# VIC20_Diag_UP.net
KiCad netlist of a schematic drawn in EAGLE
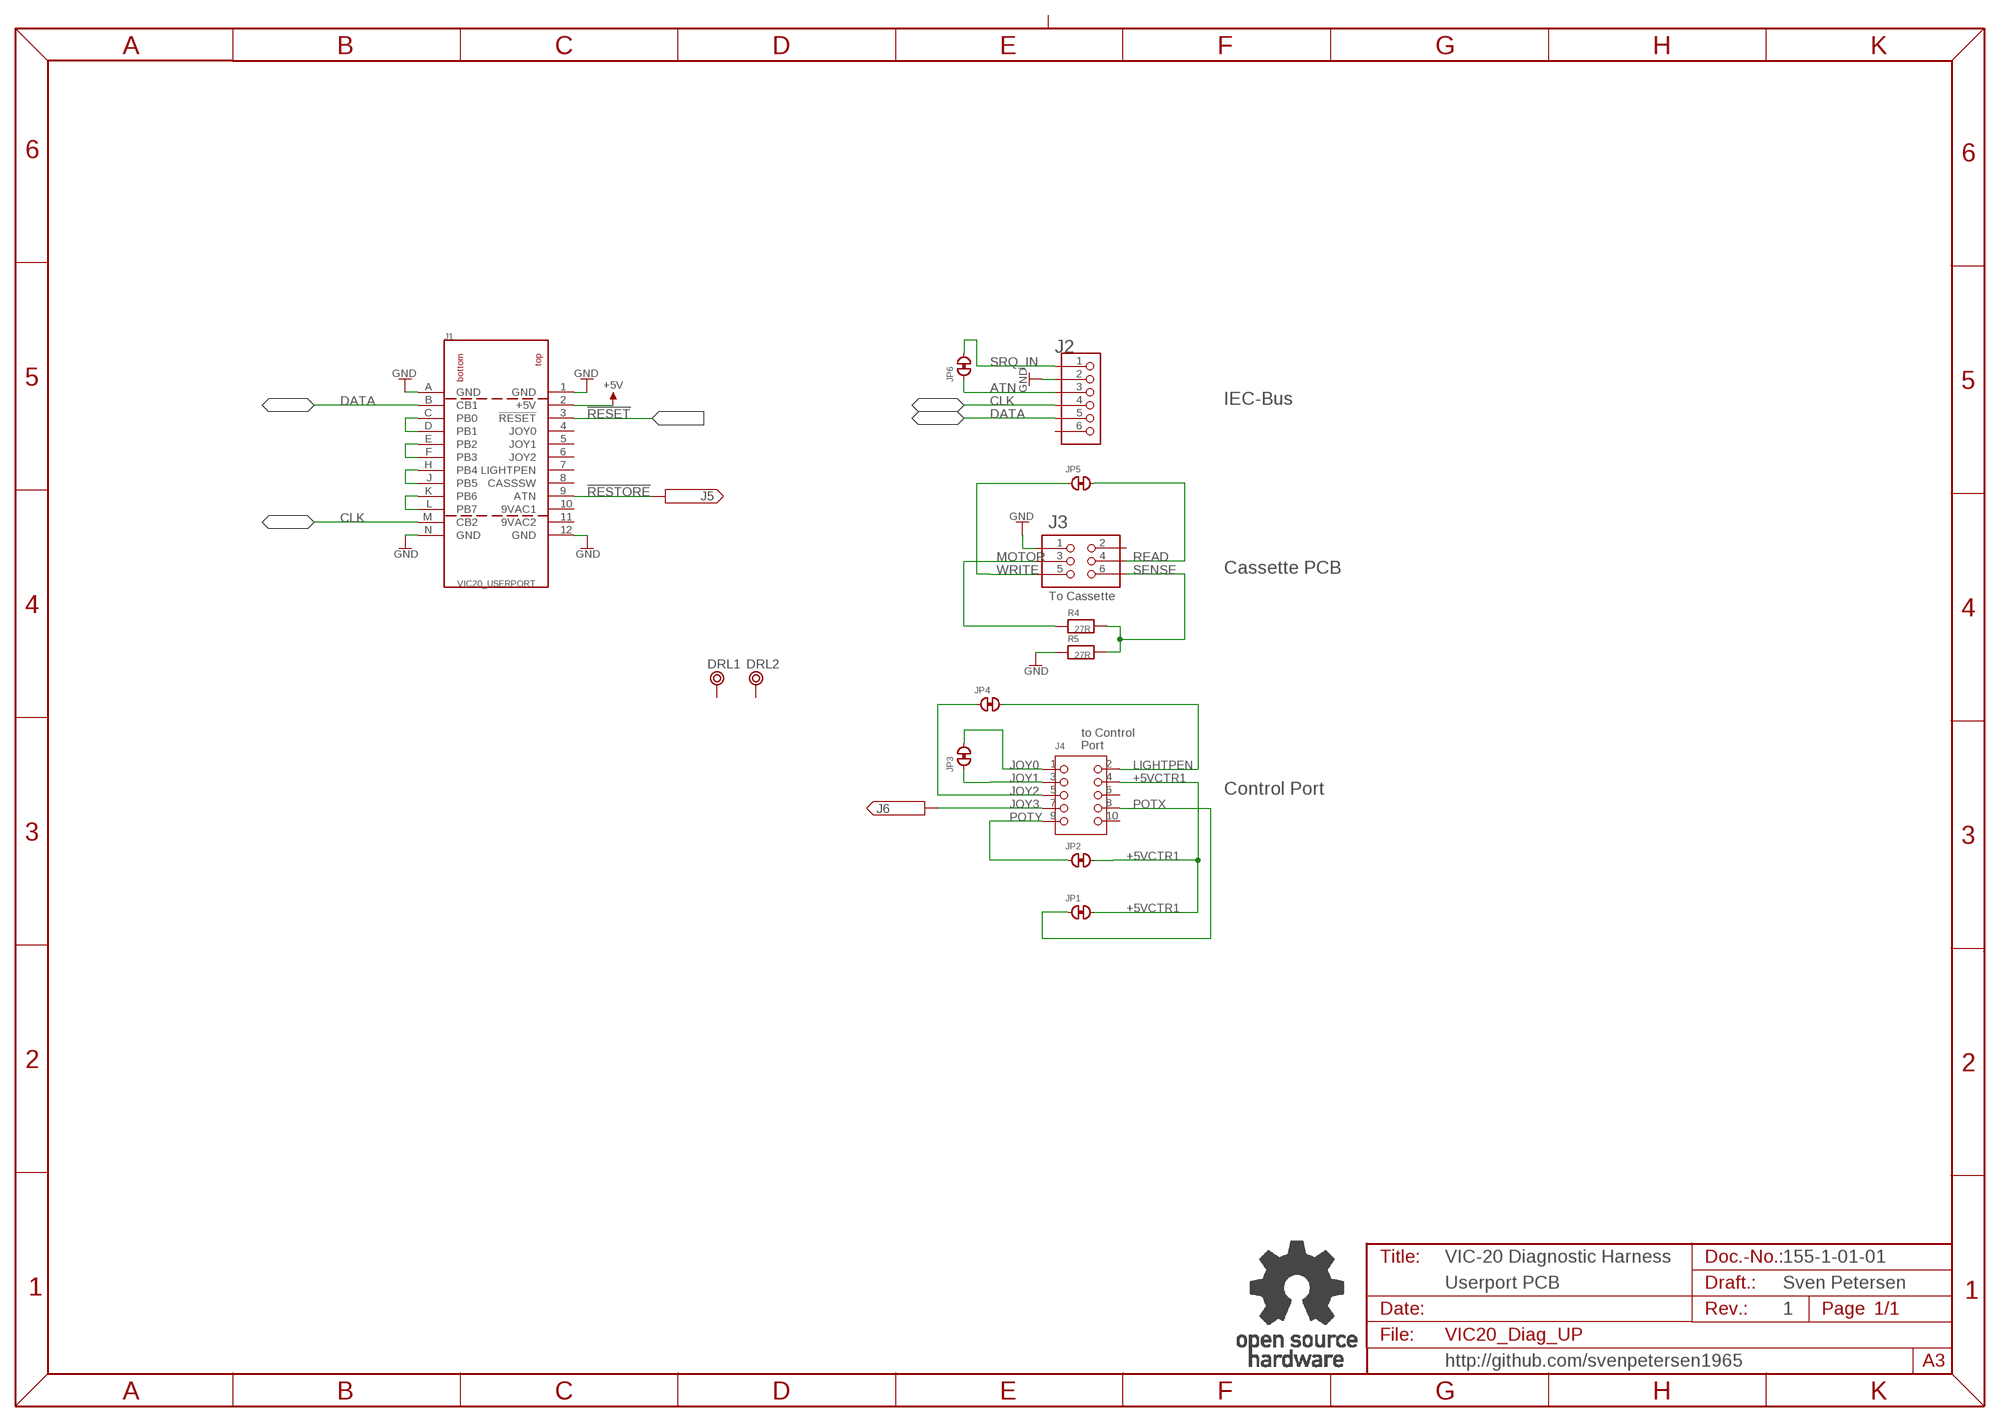
[diagram p0: schematic, sheet 1]

(export (version "E")
  (design (tool "Eeschema 10.0.6"))
  (components
    (comp (ref "DRL1")
      (value "BOHR3,5")
      (footprint "eagle-import:BOHR3,5")
      (libsource (lib "eagle-import") (part "BOHR3,5"))
    )
    (comp (ref "DRL2")
      (value "BOHR3,5")
      (footprint "eagle-import:BOHR3,5")
      (libsource (lib "eagle-import") (part "BOHR3,5"))
    )
    (comp (ref "J1")
      (value "VIC20_USERPORT")
      (footprint "eagle-import:USERPORT")
      (libsource (lib "eagle-import") (part "VIC20_USERPORT"))
    )
    (comp (ref "J2")
      (value "6410-6P")
      (footprint "eagle-import:6410-6P")
      (libsource (lib "eagle-import") (part "6410-6P"))
    )
    (comp (ref "J3")
      (value "2X03WV")
      (footprint "eagle-import:2X03WV")
      (libsource (lib "eagle-import") (part "2X03WV"))
    )
    (comp (ref "J4")
      (value "2X05WV")
      (footprint "eagle-import:2X05WV")
      (libsource (lib "eagle-import") (part "2X05WV"))
    )
    (comp (ref "J5")
      (value "PINHD-1X1")
      (footprint "eagle-import:1X01")
      (libsource (lib "eagle-import") (part "PINHD-1X1"))
    )
    (comp (ref "J6")
      (value "PINHD-1X1")
      (footprint "eagle-import:1X01")
      (libsource (lib "eagle-import") (part "PINHD-1X1"))
    )
    (comp (ref "JP1")
      (value "CLOSED")
      (footprint "eagle-import:CP_CL")
      (libsource (lib "eagle-import") (part "CLOSED"))
    )
    (comp (ref "JP2")
      (value "CLOSED")
      (footprint "eagle-import:CP_CL")
      (libsource (lib "eagle-import") (part "CLOSED"))
    )
    (comp (ref "JP3")
      (value "CLOSED")
      (footprint "eagle-import:CP_CL")
      (libsource (lib "eagle-import") (part "CLOSED"))
    )
    (comp (ref "JP4")
      (value "CLOSED")
      (footprint "eagle-import:CP_CL")
      (libsource (lib "eagle-import") (part "CLOSED"))
    )
    (comp (ref "JP5")
      (value "CLOSED")
      (footprint "eagle-import:CP_CL")
      (libsource (lib "eagle-import") (part "CLOSED"))
    )
    (comp (ref "JP6")
      (value "CLOSED")
      (footprint "eagle-import:CP_CL")
      (libsource (lib "eagle-import") (part "CLOSED"))
    )
    (comp (ref "R4")
      (value "27R")
      (footprint "eagle-import:R-10")
      (libsource (lib "eagle-import") (part "RES04"))
    )
    (comp (ref "R5")
      (value "27R")
      (footprint "eagle-import:R-10")
      (libsource (lib "eagle-import") (part "RES04"))
    )
    (comp (ref "U$2")
      (value "OPEN_SOURCE_HW")
      (footprint "eagle-import:OPENHW")
      (libsource (lib "eagle-import") (part "OPEN_SOURCE_HW"))
    )
  )
  (nets
    (net (code "1") (name "+5V") (class "Default")
      (node (ref "J1") (pin "2") (pinfunction "+5V_2") (pintype "power_in"))
    )
    (net (code "2") (name "/+5VCTR1") (class "Default")
      (node (ref "J4") (pin "4") (pinfunction "4_4") (pintype "passive"))
      (node (ref "JP1") (pin "2") (pinfunction "2_2") (pintype "passive"))
      (node (ref "JP2") (pin "2") (pinfunction "2_2") (pintype "passive"))
    )
    (net (code "3") (name "/9VAC1") (class "Default")
      (node (ref "J1") (pin "10") (pinfunction "9VAC1_10") (pintype "power_in"))
    )
    (net (code "4") (name "/9VAC2") (class "Default")
      (node (ref "J1") (pin "11") (pinfunction "9VAC2_11") (pintype "power_in"))
    )
    (net (code "5") (name "/ATN") (class "Default")
      (node (ref "J2") (pin "3") (pinfunction "3_3") (pintype "passive"))
      (node (ref "JP6") (pin "1") (pinfunction "1_1") (pintype "passive"))
    )
    (net (code "6") (name "/CLK") (class "Default")
      (node (ref "J1") (pin "M") (pinfunction "CB2_M") (pintype "bidirectional"))
      (node (ref "J2") (pin "4") (pinfunction "4_4") (pintype "passive"))
    )
    (net (code "7") (name "/DATA") (class "Default")
      (node (ref "J1") (pin "B") (pinfunction "CB1_B") (pintype "input"))
      (node (ref "J2") (pin "5") (pinfunction "5_5") (pintype "passive"))
    )
    (net (code "8") (name "/JOY0") (class "Default")
      (node (ref "J4") (pin "1") (pinfunction "1_1") (pintype "passive"))
      (node (ref "JP3") (pin "2") (pinfunction "2_2") (pintype "passive"))
    )
    (net (code "9") (name "/JOY1") (class "Default")
      (node (ref "J4") (pin "3") (pinfunction "3_3") (pintype "passive"))
      (node (ref "JP3") (pin "1") (pinfunction "1_1") (pintype "passive"))
    )
    (net (code "10") (name "/JOY2") (class "Default")
      (node (ref "J4") (pin "5") (pinfunction "5_5") (pintype "passive"))
      (node (ref "JP4") (pin "1") (pinfunction "1_1") (pintype "passive"))
    )
    (net (code "11") (name "/JOY3") (class "Default")
      (node (ref "J4") (pin "7") (pinfunction "7_7") (pintype "passive"))
      (node (ref "J6") (pin "1") (pinfunction "1_1") (pintype "passive"))
    )
    (net (code "12") (name "/LIGHTPEN") (class "Default")
      (node (ref "J4") (pin "2") (pinfunction "2_2") (pintype "passive"))
      (node (ref "JP4") (pin "2") (pinfunction "2_2") (pintype "passive"))
    )
    (net (code "13") (name "/MOTOR") (class "Default")
      (node (ref "J3") (pin "3") (pinfunction "3_3") (pintype "passive"))
      (node (ref "R4") (pin "1") (pinfunction "1_1") (pintype "passive"))
    )
    (net (code "14") (name "/POTX") (class "Default")
      (node (ref "J4") (pin "8") (pinfunction "8_8") (pintype "passive"))
      (node (ref "JP1") (pin "1") (pinfunction "1_1") (pintype "passive"))
    )
    (net (code "15") (name "/POTY") (class "Default")
      (node (ref "J4") (pin "9") (pinfunction "9_9") (pintype "passive"))
      (node (ref "JP2") (pin "1") (pinfunction "1_1") (pintype "passive"))
    )
    (net (code "16") (name "/READ") (class "Default")
      (node (ref "J3") (pin "4") (pinfunction "4_4") (pintype "passive"))
      (node (ref "JP5") (pin "2") (pinfunction "2_2") (pintype "passive"))
    )
    (net (code "17") (name "/SENSE") (class "Default")
      (node (ref "J3") (pin "6") (pinfunction "6_6") (pintype "passive"))
      (node (ref "R4") (pin "2") (pinfunction "2_2") (pintype "passive"))
      (node (ref "R5") (pin "2") (pinfunction "2_2") (pintype "passive"))
    )
    (net (code "18") (name "/SRQ_IN") (class "Default")
      (node (ref "J2") (pin "1") (pinfunction "1_1") (pintype "passive"))
      (node (ref "JP6") (pin "2") (pinfunction "2_2") (pintype "passive"))
    )
    (net (code "19") (name "/WRITE") (class "Default")
      (node (ref "J3") (pin "5") (pinfunction "5_5") (pintype "passive"))
      (node (ref "JP5") (pin "1") (pinfunction "1_1") (pintype "passive"))
    )
    (net (code "20") (name "/~{RESET}") (class "Default")
      (node (ref "J1") (pin "3") (pinfunction "~{RESET}_3") (pintype "bidirectional"))
    )
    (net (code "21") (name "/~{RESTORE}") (class "Default")
      (node (ref "J1") (pin "9") (pinfunction "ATN_9") (pintype "bidirectional"))
      (node (ref "J5") (pin "1") (pinfunction "1_1") (pintype "passive"))
    )
    (net (code "22") (name "GND") (class "Default")
      (node (ref "J1") (pin "1") (pinfunction "GND_1") (pintype "power_in"))
      (node (ref "J1") (pin "12") (pinfunction "GND_12") (pintype "power_in"))
      (node (ref "J1") (pin "A") (pinfunction "GND_A") (pintype "power_in"))
      (node (ref "J1") (pin "N") (pinfunction "GND_N") (pintype "power_in"))
      (node (ref "J2") (pin "2") (pinfunction "2_2") (pintype "passive"))
      (node (ref "J3") (pin "1") (pinfunction "1_1") (pintype "passive"))
      (node (ref "R5") (pin "1") (pinfunction "1_1") (pintype "passive"))
    )
    (net (code "23") (name "Net-(J1-PB0)") (class "Default")
      (node (ref "J1") (pin "C") (pinfunction "PB0_C") (pintype "bidirectional"))
      (node (ref "J1") (pin "D") (pinfunction "PB1_D") (pintype "bidirectional"))
    )
    (net (code "24") (name "Net-(J1-PB2)") (class "Default")
      (node (ref "J1") (pin "E") (pinfunction "PB2_E") (pintype "bidirectional"))
      (node (ref "J1") (pin "F") (pinfunction "PB3_F") (pintype "bidirectional"))
    )
    (net (code "25") (name "Net-(J1-PB4)") (class "Default")
      (node (ref "J1") (pin "H") (pinfunction "PB4_H") (pintype "bidirectional"))
      (node (ref "J1") (pin "J") (pinfunction "PB5_J") (pintype "bidirectional"))
    )
    (net (code "26") (name "Net-(J1-PB6)") (class "Default")
      (node (ref "J1") (pin "K") (pinfunction "PB6_K") (pintype "bidirectional"))
      (node (ref "J1") (pin "L") (pinfunction "PB7_L") (pintype "bidirectional"))
    )
    (net (code "27") (name "unconnected-(DRL1-PadP$1)") (class "Default")
      (node (ref "DRL1") (pin "P$1") (pinfunction "P$1_P$1") (pintype "passive"))
    )
    (net (code "28") (name "unconnected-(DRL2-PadP$1)") (class "Default")
      (node (ref "DRL2") (pin "P$1") (pinfunction "P$1_P$1") (pintype "passive"))
    )
    (net (code "29") (name "unconnected-(J1-CASSSW-Pad8)") (class "Default")
      (node (ref "J1") (pin "8") (pinfunction "CASSSW_8") (pintype "bidirectional"))
    )
    (net (code "30") (name "unconnected-(J1-JOY0-Pad4)") (class "Default")
      (node (ref "J1") (pin "4") (pinfunction "JOY0_4") (pintype "input"))
    )
    (net (code "31") (name "unconnected-(J1-JOY1-Pad5)") (class "Default")
      (node (ref "J1") (pin "5") (pinfunction "JOY1_5") (pintype "bidirectional"))
    )
    (net (code "32") (name "unconnected-(J1-JOY2-Pad6)") (class "Default")
      (node (ref "J1") (pin "6") (pinfunction "JOY2_6") (pintype "input"))
    )
    (net (code "33") (name "unconnected-(J1-LIGHTPEN-Pad7)") (class "Default")
      (node (ref "J1") (pin "7") (pinfunction "LIGHTPEN_7") (pintype "bidirectional"))
    )
    (net (code "34") (name "unconnected-(J2-Pad6)") (class "Default")
      (node (ref "J2") (pin "6") (pinfunction "6_6") (pintype "passive"))
    )
    (net (code "35") (name "unconnected-(J3-Pad2)") (class "Default")
      (node (ref "J3") (pin "2") (pinfunction "2_2") (pintype "passive"))
    )
    (net (code "36") (name "unconnected-(J4-Pad6)") (class "Default")
      (node (ref "J4") (pin "6") (pinfunction "6_6") (pintype "passive"))
    )
    (net (code "37") (name "unconnected-(J4-Pad10)") (class "Default")
      (node (ref "J4") (pin "10") (pinfunction "10_10") (pintype "passive"))
    )
  )
)
